# 01_-_STM32F101.net
KiCad netlist of a schematic drawn in Altium Designer
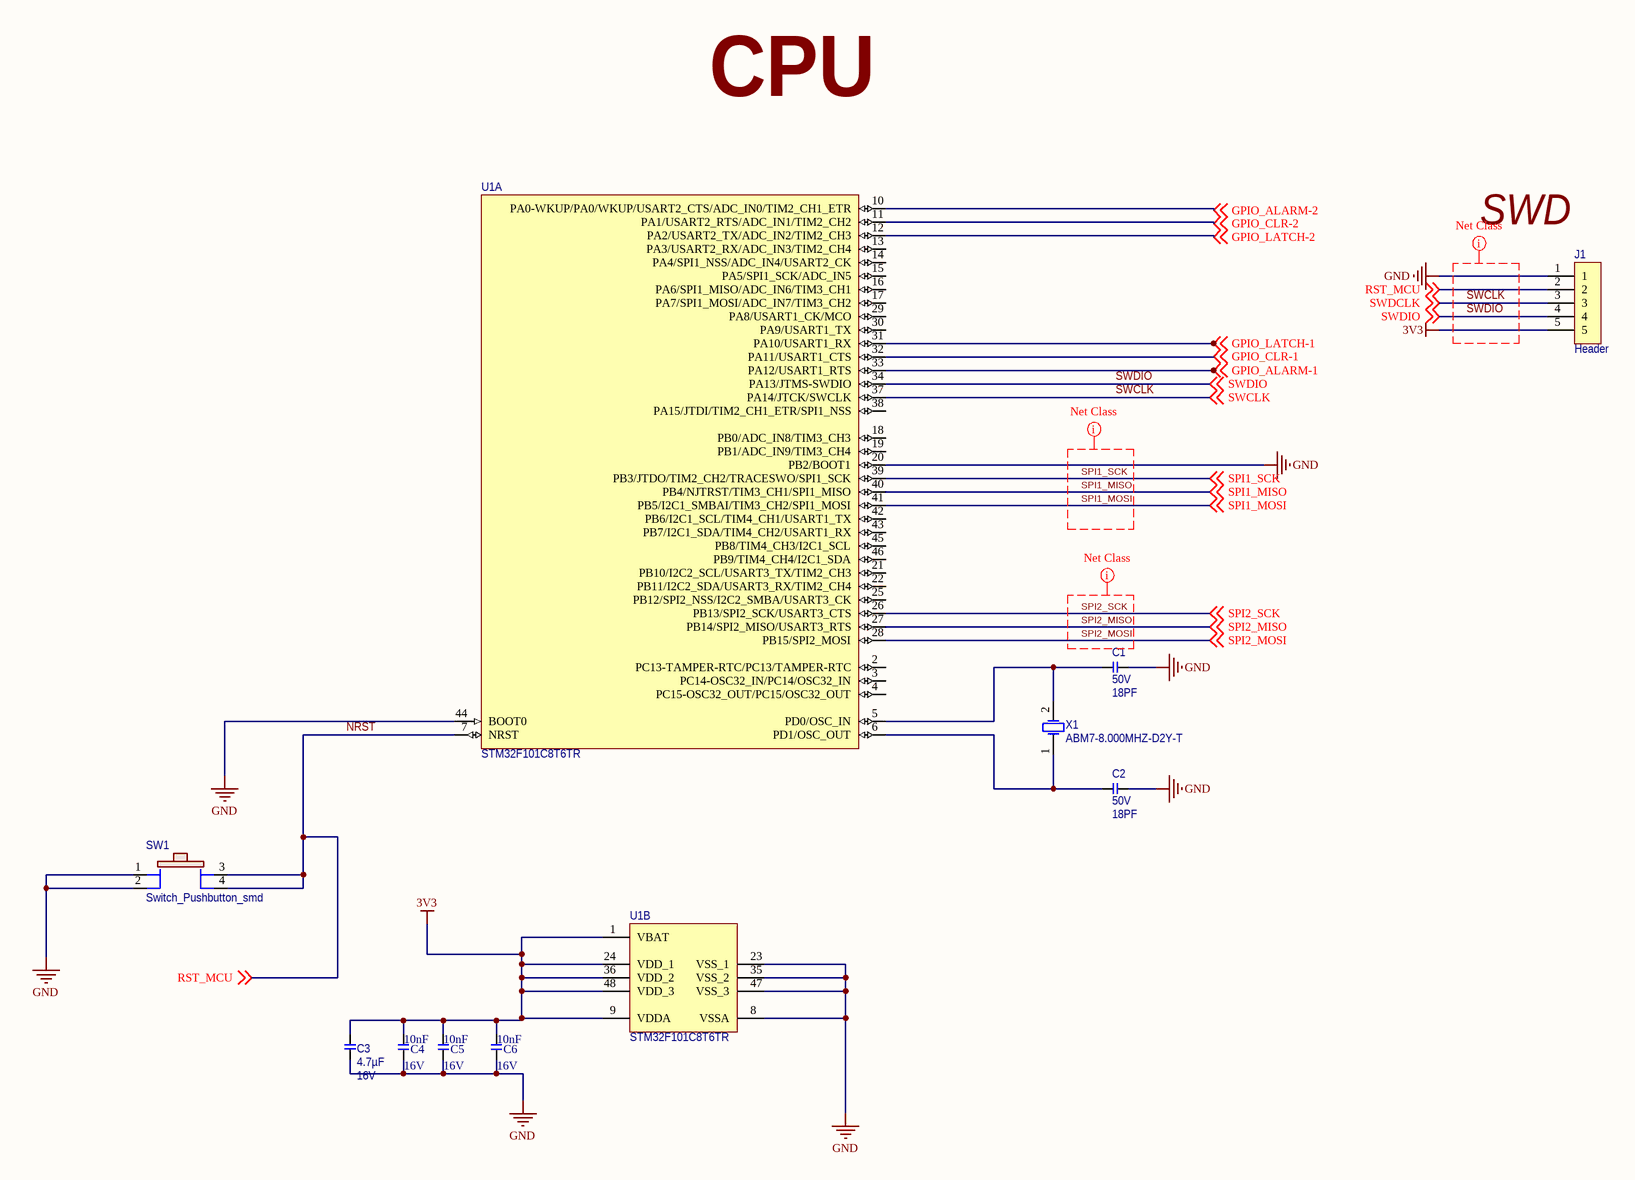
[diagram p0: [01] - STM32F101.SchDoc]

(export (version "E")
  (design (tool "Eeschema 10.0.6"))
  (components
    (comp (ref "C1")
      (value "18PF")
      (footprint "C0805")
      (description "MULTICOMP - MC0805N180J500CT - CAP, MLCC, C0G/NP0, 18PF, 50V,0805, REEL")
      (fields
        (field (name "MANUFACTURER") "Multicomp")
        (field (name "MANUFACTURER PART NUMBER") "MC0805N180J500CT")
        (field (name "VOLTAGE_RATING_DC") "50V")
        (field (name "CAPACITANCE") "18PF")
      )
      (libsource (lib "CPU_STM_080816") (part "C-18PF,50V,0805"))
    )
    (comp (ref "C2")
      (value "18PF")
      (footprint "C0805")
      (description "MULTICOMP - MC0805N180J500CT - CAP, MLCC, C0G/NP0, 18PF, 50V,0805, REEL")
      (fields
        (field (name "MANUFACTURER") "Multicomp")
        (field (name "MANUFACTURER PART NUMBER") "MC0805N180J500CT")
        (field (name "VOLTAGE_RATING_DC") "50V")
        (field (name "CAPACITANCE") "18PF")
      )
      (libsource (lib "CPU_STM_080816") (part "C-18PF,50V,0805"))
    )
    (comp (ref "C3")
      (value "4.7µF")
      (footprint "C0805")
      (description "AVX - 0805YC475KAT2A - CAP, MLCC, X7R, 4.7UF, 16V, 0805")
      (fields
        (field (name "MANUFACTURER") "AVX Corporation")
        (field (name "MANUFACTURER PART NUMBER") "0805YC475KAT2A")
        (field (name "CAPACITANCE") "4.7µF")
        (field (name "VOLTAGE - RATED") "16V")
      )
      (libsource (lib "CPU_STM_080816") (part "C-4.7UF,16V,0805"))
    )
    (comp (ref "C4")
      (value "10nF")
      (footprint "C0805")
      (description "CAP CER 10000PF 16V NP0 0805")
      (fields
        (field (name "MANUFACTURER") "AVX Corporation")
        (field (name "MANUFACTURER PART NUMBER") "0805YA103JAT2A")
        (field (name "CAPACITANCE") "10nF")
        (field (name "VOLTAGE - RATED") "16V")
      )
      (libsource (lib "CPU_STM_080816") (part "C-10NF,0805"))
    )
    (comp (ref "C5")
      (value "10nF")
      (footprint "C0805")
      (description "CAP CER 10000PF 16V NP0 0805")
      (fields
        (field (name "MANUFACTURER") "AVX Corporation")
        (field (name "MANUFACTURER PART NUMBER") "0805YA103JAT2A")
        (field (name "CAPACITANCE") "10nF")
        (field (name "VOLTAGE - RATED") "16V")
      )
      (libsource (lib "CPU_STM_080816") (part "C-10NF,0805"))
    )
    (comp (ref "C6")
      (value "10nF")
      (footprint "C0805")
      (description "CAP CER 10000PF 16V NP0 0805")
      (fields
        (field (name "MANUFACTURER") "AVX Corporation")
        (field (name "MANUFACTURER PART NUMBER") "0805YA103JAT2A")
        (field (name "CAPACITANCE") "10nF")
        (field (name "VOLTAGE - RATED") "16V")
      )
      (libsource (lib "CPU_STM_080816") (part "C-10NF,0805"))
    )
    (comp (ref "J1")
      (value "Header")
      (footprint "Header 1x5 2.54mm")
      (description "Header 1X5 2.54")
      (libsource (lib "CPU_STM_080816") (part "CON-Header 1X5 2.54MM"))
    )
    (comp (ref "SW1")
      (value "Switch_Pushbutton_smd")
      (footprint "SW_B3SL-1022P")
      (description "Switch Push Button tactile")
      (fields (field (name "TIINTPARTNUMBER") "2W0018") (field (name "MFR") "Omron"))
      (libsource (lib "CPU_STM_080816") (part "Switch_Pushbutton_smd"))
    )
    (comp (ref "U1")
      (value "IC-MC-STM32F101C8T6TR")
      (footprint "STM-LQFP48_M")
      (description "IC MCU 32BIT 64KB FLASH 48LQFP")
      (fields
        (field (name "MANUFACTURER") "STMicroelectronics")
        (field (name "MANUFACTURER PART NUMBER") "STM32F101C8T6TR")
      )
      (libsource (lib "CPU_STM_080816") (part "IC-MC-STM32F101C8T6TR"))
    )
    (comp (ref "X1")
      (value "ABM7-8.000MHZ")
      (footprint "sm_osc_mixed")
      (description "CRYSTAL 8.0000MHZ 18PF SMD")
      (fields
        (field (name "MANUFACTURER") "Abracon LLC")
        (field (name "MANUFACTURER PART NUMBER") "ABM7-8.000MHZ-D2Y-T")
      )
      (libsource (lib "CPU_STM_080816") (part "OSC-ABM7-8.000MHZ-D2Y-T"))
    )
  )
  (nets
    (net (code "1") (name "3V3") (class "Default")
      (node (ref "C3") (pin "2") (pinfunction "2_2") (pintype "passive"))
      (node (ref "C4") (pin "2") (pinfunction "2_2") (pintype "passive"))
      (node (ref "C5") (pin "2") (pinfunction "2_2") (pintype "passive"))
      (node (ref "C6") (pin "2") (pinfunction "2_2") (pintype "passive"))
      (node (ref "J1") (pin "5") (pinfunction "5_5") (pintype "passive"))
      (node (ref "U1") (pin "1") (pinfunction "VBAT_1") (pintype "power_in"))
      (node (ref "U1") (pin "24") (pinfunction "VDD_1_24") (pintype "power_in"))
      (node (ref "U1") (pin "36") (pinfunction "VDD_2_36") (pintype "power_in"))
      (node (ref "U1") (pin "48") (pinfunction "VDD_3_48") (pintype "power_in"))
      (node (ref "U1") (pin "9") (pinfunction "VDDA_9") (pintype "power_in"))
    )
    (net (code "2") (name "GND") (class "Default")
      (node (ref "C1") (pin "2") (pinfunction "2_2") (pintype "passive"))
      (node (ref "C2") (pin "2") (pinfunction "2_2") (pintype "passive"))
      (node (ref "C3") (pin "1") (pinfunction "1_1") (pintype "passive"))
      (node (ref "C4") (pin "1") (pinfunction "1_1") (pintype "passive"))
      (node (ref "C5") (pin "1") (pinfunction "1_1") (pintype "passive"))
      (node (ref "C6") (pin "1") (pinfunction "1_1") (pintype "passive"))
      (node (ref "J1") (pin "1") (pinfunction "1_1") (pintype "passive"))
      (node (ref "SW1") (pin "1") (pinfunction "1_1") (pintype "passive"))
      (node (ref "SW1") (pin "2") (pinfunction "2_2") (pintype "passive"))
      (node (ref "U1") (pin "20") (pinfunction "PB2/BOOT1_20") (pintype "bidirectional"))
      (node (ref "U1") (pin "23") (pinfunction "VSS_1_23") (pintype "power_in"))
      (node (ref "U1") (pin "35") (pinfunction "VSS_2_35") (pintype "power_in"))
      (node (ref "U1") (pin "44") (pinfunction "BOOT0_44") (pintype "input"))
      (node (ref "U1") (pin "47") (pinfunction "VSS_3_47") (pintype "power_in"))
      (node (ref "U1") (pin "8") (pinfunction "VSSA_8") (pintype "power_in"))
    )
    (net (code "3") (name "GPIO_ALARM-1") (class "Default")
      (node (ref "U1") (pin "33") (pinfunction "PA12/USART1_RTS_33") (pintype "bidirectional"))
    )
    (net (code "4") (name "GPIO_ALARM-2") (class "Default")
      (node (ref "U1") (pin "10") (pinfunction "PA0-WKUP/PA0/WKUP/USART2_CTS/ADC_IN0/TIM2_CH1_ETR_10") (pintype "bidirectional"))
    )
    (net (code "5") (name "GPIO_CLR-1") (class "Default")
      (node (ref "U1") (pin "32") (pinfunction "PA11/USART1_CTS_32") (pintype "bidirectional"))
    )
    (net (code "6") (name "GPIO_CLR-2") (class "Default")
      (node (ref "U1") (pin "11") (pinfunction "PA1/USART2_RTS/ADC_IN1/TIM2_CH2_11") (pintype "bidirectional"))
    )
    (net (code "7") (name "GPIO_LATCH-1") (class "Default")
      (node (ref "U1") (pin "31") (pinfunction "PA10/USART1_RX_31") (pintype "bidirectional"))
    )
    (net (code "8") (name "GPIO_LATCH-2") (class "Default")
      (node (ref "U1") (pin "12") (pinfunction "PA2/USART2_TX/ADC_IN2/TIM2_CH3_12") (pintype "bidirectional"))
    )
    (net (code "9") (name "Net-(U1A-PD0{slash}OSC_IN)") (class "Default")
      (node (ref "C1") (pin "1") (pinfunction "1_1") (pintype "passive"))
      (node (ref "U1") (pin "5") (pinfunction "PD0/OSC_IN_5") (pintype "bidirectional"))
      (node (ref "X1") (pin "2") (pinfunction "OSC2_2") (pintype "passive"))
    )
    (net (code "10") (name "Net-(U1A-PD1{slash}OSC_OUT)") (class "Default")
      (node (ref "C2") (pin "1") (pinfunction "1_1") (pintype "passive"))
      (node (ref "U1") (pin "6") (pinfunction "PD1/OSC_OUT_6") (pintype "bidirectional"))
      (node (ref "X1") (pin "1") (pinfunction "OSC1_1") (pintype "passive"))
    )
    (net (code "11") (name "RST_MCU") (class "Default")
      (node (ref "J1") (pin "2") (pinfunction "2_2") (pintype "passive"))
      (node (ref "SW1") (pin "3") (pinfunction "3_3") (pintype "passive"))
      (node (ref "SW1") (pin "4") (pinfunction "4_4") (pintype "passive"))
      (node (ref "U1") (pin "7") (pinfunction "NRST_7") (pintype "bidirectional"))
    )
    (net (code "12") (name "SPI1_MISO") (class "Default")
      (node (ref "U1") (pin "40") (pinfunction "PB4/NJTRST/TIM3_CH1/SPI1_MISO_40") (pintype "bidirectional"))
    )
    (net (code "13") (name "SPI1_MOSI") (class "Default")
      (node (ref "U1") (pin "41") (pinfunction "PB5/I2C1_SMBAI/TIM3_CH2/SPI1_MOSI_41") (pintype "bidirectional"))
    )
    (net (code "14") (name "SPI1_SCK") (class "Default")
      (node (ref "U1") (pin "39") (pinfunction "PB3/JTDO/TIM2_CH2/TRACESWO/SPI1_SCK_39") (pintype "bidirectional"))
    )
    (net (code "15") (name "SPI2_MISO") (class "Default")
      (node (ref "U1") (pin "27") (pinfunction "PB14/SPI2_MISO/USART3_RTS_27") (pintype "bidirectional"))
    )
    (net (code "16") (name "SPI2_MOSI") (class "Default")
      (node (ref "U1") (pin "28") (pinfunction "PB15/SPI2_MOSI_28") (pintype "bidirectional"))
    )
    (net (code "17") (name "SPI2_SCK") (class "Default")
      (node (ref "U1") (pin "26") (pinfunction "PB13/SPI2_SCK/USART3_CTS_26") (pintype "bidirectional"))
    )
    (net (code "18") (name "SWCLK") (class "Default")
      (node (ref "J1") (pin "3") (pinfunction "3_3") (pintype "passive"))
      (node (ref "U1") (pin "37") (pinfunction "PA14/JTCK/SWCLK_37") (pintype "bidirectional"))
    )
    (net (code "19") (name "SWDIO") (class "Default")
      (node (ref "J1") (pin "4") (pinfunction "4_4") (pintype "passive"))
      (node (ref "U1") (pin "34") (pinfunction "PA13/JTMS-SWDIO_34") (pintype "bidirectional"))
    )
    (net (code "20") (name "unconnected-(U1A-PA3{slash}USART2_RX{slash}ADC_IN3{slash}TIM2_CH4-Pad13)") (class "Default")
      (node (ref "U1") (pin "13") (pinfunction "PA3/USART2_RX/ADC_IN3/TIM2_CH4_13") (pintype "bidirectional"))
    )
    (net (code "21") (name "unconnected-(U1A-PA4{slash}SPI1_NSS{slash}ADC_IN4{slash}USART2_CK-Pad14)") (class "Default")
      (node (ref "U1") (pin "14") (pinfunction "PA4/SPI1_NSS/ADC_IN4/USART2_CK_14") (pintype "bidirectional"))
    )
    (net (code "22") (name "unconnected-(U1A-PA5{slash}SPI1_SCK{slash}ADC_IN5-Pad15)") (class "Default")
      (node (ref "U1") (pin "15") (pinfunction "PA5/SPI1_SCK/ADC_IN5_15") (pintype "bidirectional"))
    )
    (net (code "23") (name "unconnected-(U1A-PA6{slash}SPI1_MISO{slash}ADC_IN6{slash}TIM3_CH1-Pad16)") (class "Default")
      (node (ref "U1") (pin "16") (pinfunction "PA6/SPI1_MISO/ADC_IN6/TIM3_CH1_16") (pintype "bidirectional"))
    )
    (net (code "24") (name "unconnected-(U1A-PA7{slash}SPI1_MOSI{slash}ADC_IN7{slash}TIM3_CH2-Pad17)") (class "Default")
      (node (ref "U1") (pin "17") (pinfunction "PA7/SPI1_MOSI/ADC_IN7/TIM3_CH2_17") (pintype "bidirectional"))
    )
    (net (code "25") (name "unconnected-(U1A-PA8{slash}USART1_CK{slash}MCO-Pad29)") (class "Default")
      (node (ref "U1") (pin "29") (pinfunction "PA8/USART1_CK/MCO_29") (pintype "bidirectional"))
    )
    (net (code "26") (name "unconnected-(U1A-PA9{slash}USART1_TX-Pad30)") (class "Default")
      (node (ref "U1") (pin "30") (pinfunction "PA9/USART1_TX_30") (pintype "bidirectional"))
    )
    (net (code "27") (name "unconnected-(U1A-PA15{slash}JTDI{slash}TIM2_CH1_ETR{slash}SPI1_NSS-Pad38)") (class "Default")
      (node (ref "U1") (pin "38") (pinfunction "PA15/JTDI/TIM2_CH1_ETR/SPI1_NSS_38") (pintype "bidirectional"))
    )
    (net (code "28") (name "unconnected-(U1A-PB0{slash}ADC_IN8{slash}TIM3_CH3-Pad18)") (class "Default")
      (node (ref "U1") (pin "18") (pinfunction "PB0/ADC_IN8/TIM3_CH3_18") (pintype "bidirectional"))
    )
    (net (code "29") (name "unconnected-(U1A-PB1{slash}ADC_IN9{slash}TIM3_CH4-Pad19)") (class "Default")
      (node (ref "U1") (pin "19") (pinfunction "PB1/ADC_IN9/TIM3_CH4_19") (pintype "bidirectional"))
    )
    (net (code "30") (name "unconnected-(U1A-PB6{slash}I2C1_SCL{slash}TIM4_CH1{slash}USART1_TX-Pad42)") (class "Default")
      (node (ref "U1") (pin "42") (pinfunction "PB6/I2C1_SCL/TIM4_CH1/USART1_TX_42") (pintype "bidirectional"))
    )
    (net (code "31") (name "unconnected-(U1A-PB7{slash}I2C1_SDA{slash}TIM4_CH2{slash}USART1_RX-Pad43)") (class "Default")
      (node (ref "U1") (pin "43") (pinfunction "PB7/I2C1_SDA/TIM4_CH2/USART1_RX_43") (pintype "bidirectional"))
    )
    (net (code "32") (name "unconnected-(U1A-PB8{slash}TIM4_CH3{slash}I2C1_SCL-Pad45)") (class "Default")
      (node (ref "U1") (pin "45") (pinfunction "PB8/TIM4_CH3/I2C1_SCL_45") (pintype "bidirectional"))
    )
    (net (code "33") (name "unconnected-(U1A-PB9{slash}TIM4_CH4{slash}I2C1_SDA-Pad46)") (class "Default")
      (node (ref "U1") (pin "46") (pinfunction "PB9/TIM4_CH4/I2C1_SDA_46") (pintype "bidirectional"))
    )
    (net (code "34") (name "unconnected-(U1A-PB10{slash}I2C2_SCL{slash}USART3_TX{slash}TIM2_CH3-Pad21)") (class "Default")
      (node (ref "U1") (pin "21") (pinfunction "PB10/I2C2_SCL/USART3_TX/TIM2_CH3_21") (pintype "bidirectional"))
    )
    (net (code "35") (name "unconnected-(U1A-PB11{slash}I2C2_SDA{slash}USART3_RX{slash}TIM2_CH4-Pad22)") (class "Default")
      (node (ref "U1") (pin "22") (pinfunction "PB11/I2C2_SDA/USART3_RX/TIM2_CH4_22") (pintype "bidirectional"))
    )
    (net (code "36") (name "unconnected-(U1A-PB12{slash}SPI2_NSS{slash}I2C2_SMBA{slash}USART3_CK-Pad25)") (class "Default")
      (node (ref "U1") (pin "25") (pinfunction "PB12/SPI2_NSS/I2C2_SMBA/USART3_CK_25") (pintype "bidirectional"))
    )
    (net (code "37") (name "unconnected-(U1A-PC13-TAMPER-RTC{slash}PC13{slash}TAMPER-RTC-Pad2)") (class "Default")
      (node (ref "U1") (pin "2") (pinfunction "PC13-TAMPER-RTC/PC13/TAMPER-RTC_2") (pintype "bidirectional"))
    )
    (net (code "38") (name "unconnected-(U1A-PC14-OSC32_IN{slash}PC14{slash}OSC32_IN-Pad3)") (class "Default")
      (node (ref "U1") (pin "3") (pinfunction "PC14-OSC32_IN/PC14/OSC32_IN_3") (pintype "bidirectional"))
    )
    (net (code "39") (name "unconnected-(U1A-PC15-OSC32_OUT{slash}PC15{slash}OSC32_OUT-Pad4)") (class "Default")
      (node (ref "U1") (pin "4") (pinfunction "PC15-OSC32_OUT/PC15/OSC32_OUT_4") (pintype "bidirectional"))
    )
  )
)
